# v1.net
KiCad netlist of a schematic drawn in EAGLE
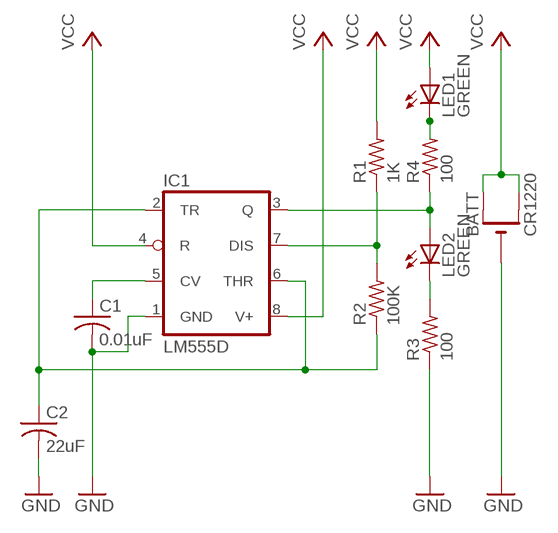
[diagram p0: schematic, sheet 1]

(export (version "E")
  (design (tool "Eeschema 10.0.6"))
  (components
    (comp (ref "BATT")
      (value "CR1220")
      (footprint "eagle-import:CR1220-SMD")
      (libsource (lib "eagle-import") (part "CR1220SMT"))
    )
    (comp (ref "C1")
      (value "0.01uF")
      (footprint "eagle-import:C0805")
      (fields (field (name "MF") "AVX CORPORATION") (field (name "MPN") "08051C103KAT2A"))
      (libsource (lib "eagle-import") (part "C-USC0805"))
    )
    (comp (ref "C2")
      (value "22uF")
      (footprint "eagle-import:C0805")
      (fields (field (name "MPN") "C2012X5R1A226K125AB"))
      (libsource (lib "eagle-import") (part "C-USC0805"))
    )
    (comp (ref "IC1")
      (value "LM555D")
      (footprint "eagle-import:SO08")
      (fields (field (name "MF") "FAIRCHILD SEMICONDUCTOR") (field (name "MPN") "LM555CM"))
      (libsource (lib "eagle-import") (part "555DLM"))
    )
    (comp (ref "LED1")
      (value "GREEN")
      (footprint "eagle-import:CHIP-LED0805")
      (fields (field (name "MPN") "150080VS75000"))
      (libsource (lib "eagle-import") (part "LEDCHIP-LED0805"))
    )
    (comp (ref "LED2")
      (value "GREEN")
      (footprint "eagle-import:CHIP-LED0805")
      (fields (field (name "MPN") "150080VS75000"))
      (libsource (lib "eagle-import") (part "LEDCHIP-LED0805"))
    )
    (comp (ref "R1")
      (value "1K")
      (footprint "eagle-import:R0805")
      (fields (field (name "MPN") "ERA-6APB102P"))
      (libsource (lib "eagle-import") (part "R-US_R0805"))
    )
    (comp (ref "R2")
      (value "100K")
      (footprint "eagle-import:R0805")
      (fields (field (name "MF") "VISHAY/DALE") (field (name "MPN") "CRCW0805100KFKTA"))
      (libsource (lib "eagle-import") (part "R-US_R0805"))
    )
    (comp (ref "R3")
      (value "100")
      (footprint "eagle-import:R0805")
      (fields (field (name "MF") "VISHAY/DALE") (field (name "MPN") "CRCW0805100RJNEA"))
      (libsource (lib "eagle-import") (part "R-US_R0805"))
    )
    (comp (ref "R4")
      (value "100")
      (footprint "eagle-import:R0805")
      (fields (field (name "MF") "VISHAY/DALE") (field (name "MPN") "CRCW0805100RJNEA"))
      (libsource (lib "eagle-import") (part "R-US_R0805"))
    )
  )
  (nets
    (net (code "1") (name "GND") (class "Default")
      (node (ref "BATT") (pin "-") (pinfunction "-_-") (pintype "passive"))
      (node (ref "C1") (pin "2") (pinfunction "2_2") (pintype "passive"))
      (node (ref "C2") (pin "2") (pinfunction "2_2") (pintype "passive"))
      (node (ref "IC1") (pin "1") (pinfunction "GND_1") (pintype "power_in"))
      (node (ref "R3") (pin "1") (pinfunction "1_1") (pintype "passive"))
    )
    (net (code "2") (name "Net-(IC1-CV)") (class "Default")
      (node (ref "C1") (pin "1") (pinfunction "1_1") (pintype "passive"))
      (node (ref "IC1") (pin "5") (pinfunction "CV_5") (pintype "input"))
    )
    (net (code "3") (name "Net-(IC1-DIS)") (class "Default")
      (node (ref "IC1") (pin "7") (pinfunction "DIS_7") (pintype "input"))
      (node (ref "R1") (pin "1") (pinfunction "1_1") (pintype "passive"))
      (node (ref "R2") (pin "2") (pinfunction "2_2") (pintype "passive"))
    )
    (net (code "4") (name "Net-(IC1-Q)") (class "Default")
      (node (ref "IC1") (pin "3") (pinfunction "Q_3") (pintype "output"))
      (node (ref "LED2") (pin "A") (pinfunction "A_A") (pintype "passive"))
      (node (ref "R4") (pin "1") (pinfunction "1_1") (pintype "passive"))
    )
    (net (code "5") (name "Net-(IC1-THR)") (class "Default")
      (node (ref "C2") (pin "1") (pinfunction "1_1") (pintype "passive"))
      (node (ref "IC1") (pin "2") (pinfunction "TR_2") (pintype "input"))
      (node (ref "IC1") (pin "6") (pinfunction "THR_6") (pintype "input"))
      (node (ref "R2") (pin "1") (pinfunction "1_1") (pintype "passive"))
    )
    (net (code "6") (name "Net-(LED1-PadC)") (class "Default")
      (node (ref "LED1") (pin "C") (pinfunction "C_C") (pintype "passive"))
      (node (ref "R4") (pin "2") (pinfunction "2_2") (pintype "passive"))
    )
    (net (code "7") (name "Net-(LED2-PadC)") (class "Default")
      (node (ref "LED2") (pin "C") (pinfunction "C_C") (pintype "passive"))
      (node (ref "R3") (pin "2") (pinfunction "2_2") (pintype "passive"))
    )
    (net (code "8") (name "VCC") (class "Default")
      (node (ref "BATT") (pin "+$1") (pinfunction "+_+$1") (pintype "passive"))
      (node (ref "BATT") (pin "+$2") (pinfunction "+1_+$2") (pintype "passive"))
      (node (ref "IC1") (pin "4") (pinfunction "R_4") (pintype "input"))
      (node (ref "IC1") (pin "8") (pinfunction "V+_8") (pintype "power_in"))
      (node (ref "LED1") (pin "A") (pinfunction "A_A") (pintype "passive"))
      (node (ref "R1") (pin "2") (pinfunction "2_2") (pintype "passive"))
    )
  )
)
